# TOP.net
KiCad netlist of a schematic drawn in Altium Designer
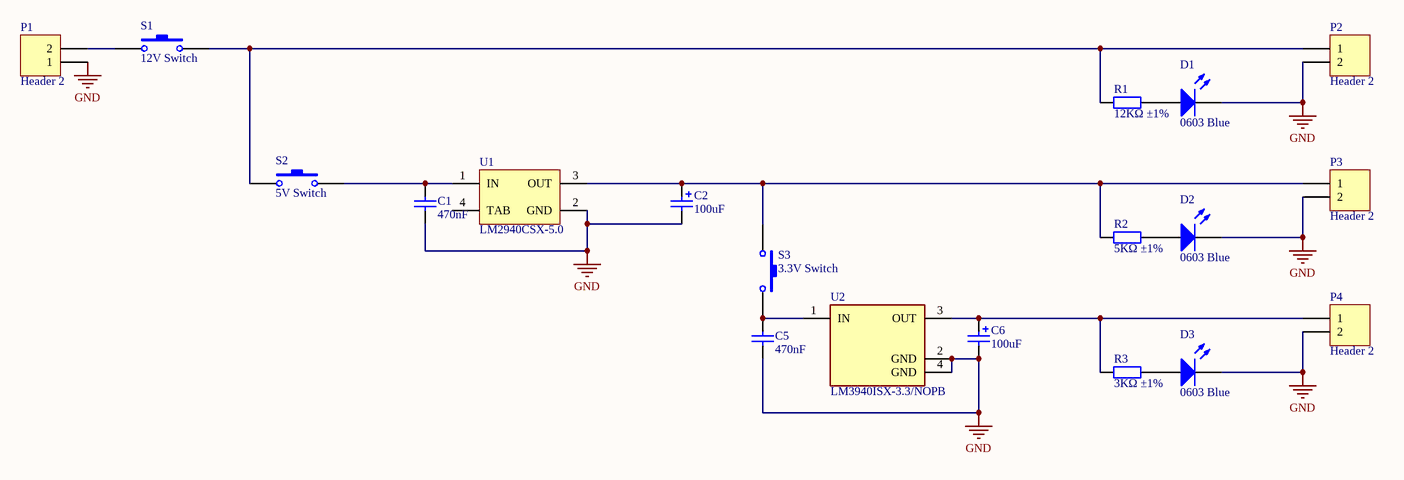
[diagram p0: TOP.SchDoc]

(export (version "E")
  (design (tool "Eeschema 10.0.6"))
  (components
    (comp (ref "C1")
      (value "470nF")
      (footprint "1206_C")
      (description "Chip capacitors")
      (fields
        (field (name "MANUFACTURER") "Guangdong Fenghua Advanced Tech")
        (field (name "PARTNUMBER") "1206B474K500NT")
      )
      (libsource (lib "Cap") (part "1206 470nF (474) 10% 50V"))
    )
    (comp (ref "C2")
      (value "100uF")
      (footprint "CASE-B_3528")
      (description "Tantalum capacitor")
      (fields (field (name "MANUFACTURER") "AVX") (field (name "PARTNUMBER") "TAJB107K006RNJ"))
      (libsource (lib "Cap") (part "3528 100uF (107) 10% 6.3V"))
    )
    (comp (ref "C5")
      (value "470nF")
      (footprint "0805_C")
      (description "Chip capacitors")
      (fields
        (field (name "MANUFACTURER") "Samsung Electro-Mechanics")
        (field (name "PARTNUMBER") "CL21B474KBFNNNE")
      )
      (libsource (lib "Cap") (part "0805 470nF (474) 10% 50V"))
    )
    (comp (ref "C6")
      (value "100uF")
      (footprint "CASE-B_3528")
      (description "Tantalum capacitor")
      (fields (field (name "MANUFACTURER") "AVX") (field (name "PARTNUMBER") "TAJB107K006RNJ"))
      (libsource (lib "Cap") (part "3528 100uF (107) 10% 6.3V"))
    )
    (comp (ref "D1")
      (value "0603 Blue")
      (footprint "0603_LED_S1")
      (description "LED")
      (libsource (lib "LED") (part "0603 LED Blue"))
    )
    (comp (ref "D2")
      (value "0603 Blue")
      (footprint "0603_LED_S1")
      (description "LED")
      (libsource (lib "LED") (part "0603 LED Blue"))
    )
    (comp (ref "D3")
      (value "0603 Blue")
      (footprint "0603_LED_S1")
      (description "LED")
      (libsource (lib "LED") (part "0603 LED Blue"))
    )
    (comp (ref "P1")
      (value "Header 2")
      (footprint "HDR1X2")
      (description "Header, 2-Pin")
      (fields (field (name "PUBLISHER") "Altium Limited"))
      (libsource (lib "Miscellaneous Connectors") (part "Header 2"))
    )
    (comp (ref "P2")
      (value "Header 2")
      (footprint "HDR1X2")
      (description "Header, 2-Pin")
      (fields (field (name "PUBLISHER") "Altium Limited"))
      (libsource (lib "") (part "Header 2_1"))
    )
    (comp (ref "P3")
      (value "Header 2")
      (footprint "HDR1X2")
      (description "Header, 2-Pin")
      (fields (field (name "PUBLISHER") "Altium Limited"))
      (libsource (lib "") (part "Header 2_1"))
    )
    (comp (ref "P4")
      (value "Header 2")
      (footprint "HDR1X2")
      (description "Header, 2-Pin")
      (fields (field (name "PUBLISHER") "Altium Limited"))
      (libsource (lib "") (part "Header 2_1"))
    )
    (comp (ref "R1")
      (value "12KΩ ±1%")
      (footprint "0805_R")
      (description "Chip resistor")
      (fields (field (name "MANUFACTURER") "Uniroyal Elec") (field (name "POWER") "1/8W"))
      (libsource (lib "RES") (part "0805 1M (1004) 1%"))
    )
    (comp (ref "R2")
      (value "5KΩ ±1%")
      (footprint "0805_R")
      (description "Chip resistor")
      (fields (field (name "MANUFACTURER") "Uniroyal Elec") (field (name "POWER") "1/8W"))
      (libsource (lib "RES") (part "0805 1M (1004) 1%"))
    )
    (comp (ref "R3")
      (value "3KΩ ±1%")
      (footprint "0805_R")
      (description "Chip resistor")
      (fields (field (name "MANUFACTURER") "Uniroyal Elec") (field (name "POWER") "1/8W"))
      (libsource (lib "RES") (part "0805 1M (1004) 1%"))
    )
    (comp (ref "S1")
      (value "12V Switch")
      (footprint "SPST-2")
      (description "Switch")
      (fields (field (name "PUBLISHER") "Altium Limited"))
      (libsource (lib "Miscellaneous Devices") (part "SW-PB"))
    )
    (comp (ref "S2")
      (value "5V Switch")
      (footprint "SPST-2")
      (description "Switch")
      (fields (field (name "PUBLISHER") "Altium Limited"))
      (libsource (lib "Miscellaneous Devices") (part "SW-PB"))
    )
    (comp (ref "S3")
      (value "3.3V Switch")
      (footprint "SPST-2")
      (description "Switch")
      (fields (field (name "PUBLISHER") "Altium Limited"))
      (libsource (lib "Miscellaneous Devices") (part "SW-PB"))
    )
    (comp (ref "U1")
      (value "LM2940CSX-5.0")
      (footprint "KTT0003B_L")
      (description "1A Low Dropout Regulator, 3-pin TO-263")
      (fields (field (name "MANUFACTURER") "Texas Instruments"))
      (libsource (lib "Altium Content Vault") (part "PM-REG-LM2940-TO4"))
    )
    (comp (ref "U2")
      (value "LM3940ISX-3.3/NOPB")
      (footprint "FP-KTT0003B-MFG")
      (description "IC REG LIN 3.3V 1A DDPAK/TO263-3")
      (fields
        (field (name "OCTOPART") "https://octopart.com/lm3940isx-3.3%2Fnopb-texas+instruments-24814218")
        (field (name "MANUFACTURER") "Texas Instruments")
      )
      (libsource (lib "Altium Content Vault") (part "5d75afe1045818d72111deb72d0ea28"))
    )
  )
  (nets
    (net (code "1") (name "GND") (class "Default")
      (node (ref "C1") (pin "1") (pinfunction "1_1") (pintype "passive"))
      (node (ref "C2") (pin "2") (pinfunction "2_2") (pintype "passive"))
      (node (ref "C5") (pin "1") (pinfunction "1_1") (pintype "passive"))
      (node (ref "C6") (pin "2") (pinfunction "2_2") (pintype "passive"))
      (node (ref "D1") (pin "K") (pinfunction "K_K") (pintype "passive"))
      (node (ref "D2") (pin "K") (pinfunction "K_K") (pintype "passive"))
      (node (ref "D3") (pin "K") (pinfunction "K_K") (pintype "passive"))
      (node (ref "P1") (pin "1") (pinfunction "1_1") (pintype "passive"))
      (node (ref "P2") (pin "2") (pinfunction "2_2") (pintype "passive"))
      (node (ref "P3") (pin "2") (pinfunction "2_2") (pintype "passive"))
      (node (ref "P4") (pin "2") (pinfunction "2_2") (pintype "passive"))
      (node (ref "U1") (pin "2") (pinfunction "GND_2") (pintype "power_in"))
      (node (ref "U2") (pin "2") (pinfunction "GND_2") (pintype "power_in"))
      (node (ref "U2") (pin "4") (pinfunction "GND_4") (pintype "power_in"))
    )
    (net (code "2") (name "Net-(D1-PadA)") (class "Default")
      (node (ref "D1") (pin "A") (pinfunction "A_A") (pintype "passive"))
      (node (ref "R1") (pin "2") (pinfunction "2_2") (pintype "passive"))
    )
    (net (code "3") (name "Net-(D2-PadA)") (class "Default")
      (node (ref "D2") (pin "A") (pinfunction "A_A") (pintype "passive"))
      (node (ref "R2") (pin "2") (pinfunction "2_2") (pintype "passive"))
    )
    (net (code "4") (name "Net-(D3-PadA)") (class "Default")
      (node (ref "D3") (pin "A") (pinfunction "A_A") (pintype "passive"))
      (node (ref "R3") (pin "2") (pinfunction "2_2") (pintype "passive"))
    )
    (net (code "5") (name "Net-(P1-Pad2)") (class "Default")
      (node (ref "P1") (pin "2") (pinfunction "2_2") (pintype "passive"))
      (node (ref "S1") (pin "1") (pinfunction "1_1") (pintype "passive"))
    )
    (net (code "6") (name "Net-(P2-Pad1)") (class "Default")
      (node (ref "P2") (pin "1") (pinfunction "1_1") (pintype "passive"))
      (node (ref "R1") (pin "1") (pinfunction "1_1") (pintype "passive"))
      (node (ref "S1") (pin "2") (pinfunction "2_2") (pintype "passive"))
      (node (ref "S2") (pin "1") (pinfunction "1_1") (pintype "passive"))
    )
    (net (code "7") (name "Net-(U1-IN)") (class "Default")
      (node (ref "C1") (pin "2") (pinfunction "2_2") (pintype "passive"))
      (node (ref "S2") (pin "2") (pinfunction "2_2") (pintype "passive"))
      (node (ref "U1") (pin "1") (pinfunction "IN_1") (pintype "power_in"))
    )
    (net (code "8") (name "Net-(U1-OUT)") (class "Default")
      (node (ref "C2") (pin "1") (pinfunction "1_1") (pintype "passive"))
      (node (ref "P3") (pin "1") (pinfunction "1_1") (pintype "passive"))
      (node (ref "R2") (pin "1") (pinfunction "1_1") (pintype "passive"))
      (node (ref "S3") (pin "1") (pinfunction "1_1") (pintype "passive"))
      (node (ref "U1") (pin "3") (pinfunction "OUT_3") (pintype "power_in"))
    )
    (net (code "9") (name "Net-(U2-IN)") (class "Default")
      (node (ref "C5") (pin "2") (pinfunction "2_2") (pintype "passive"))
      (node (ref "S3") (pin "2") (pinfunction "2_2") (pintype "passive"))
      (node (ref "U2") (pin "1") (pinfunction "IN_1") (pintype "power_in"))
    )
    (net (code "10") (name "Net-(U2-OUT)") (class "Default")
      (node (ref "C6") (pin "1") (pinfunction "1_1") (pintype "passive"))
      (node (ref "P4") (pin "1") (pinfunction "1_1") (pintype "passive"))
      (node (ref "R3") (pin "1") (pinfunction "1_1") (pintype "passive"))
      (node (ref "U2") (pin "3") (pinfunction "OUT_3") (pintype "power_in"))
    )
    (net (code "11") (name "unconnected-(U1-TAB-Pad4)") (class "Default")
      (node (ref "U1") (pin "4") (pinfunction "TAB_4") (pintype "power_in"))
    )
  )
)
